# ProDocument_PCB6.net
KiCad netlist of a schematic drawn in EasyEDA Pro
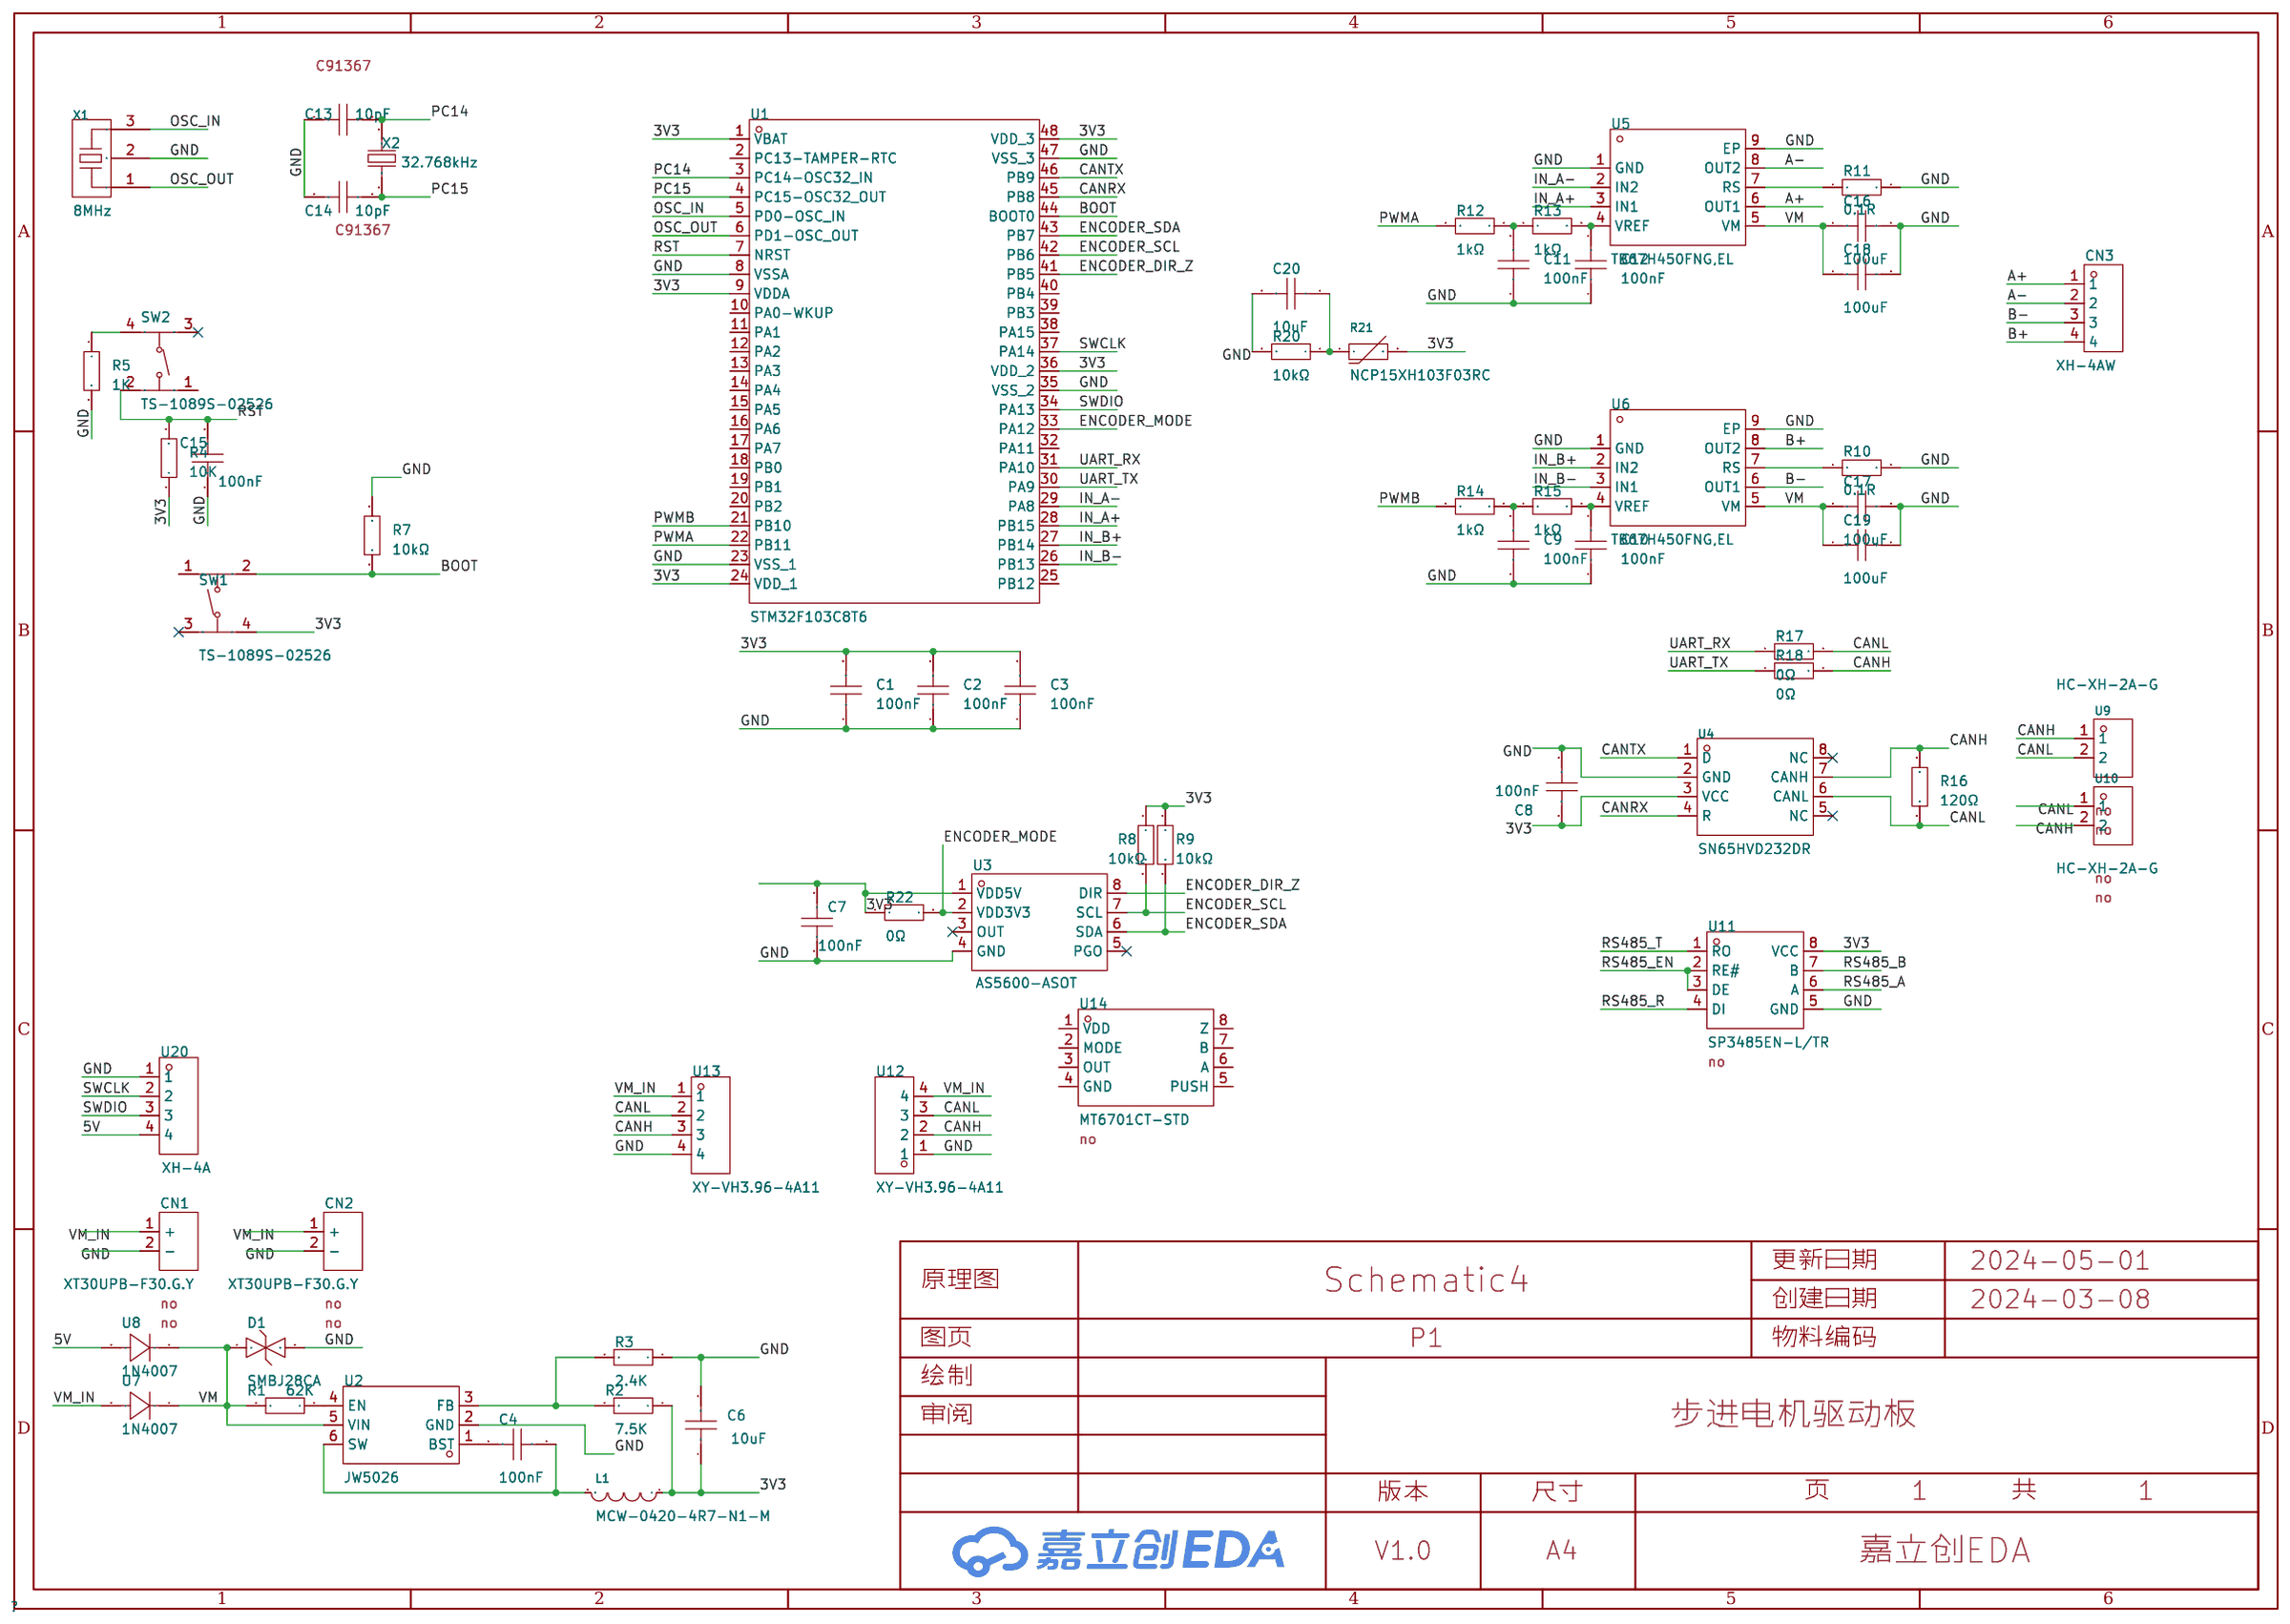
[diagram p0: schematic sheet]

(export (version "E")
  (design (tool "Eeschema 10.0.6"))
  (components
    (comp (ref "C1")
      (value "100nF")
      (description "容值:100nF;精度:±10%;额定电压:50V;材质(温度系数):X7R;")
      (fields (field (name "Manufacturer Part") "0603B104K500NT") (field (name "Manufacturer") "FH(风华)"))
      (libsource (lib "easyedapro") (part "CapAcitance"))
    )
    (comp (ref "C2")
      (value "100nF")
      (description "容值:100nF;精度:±10%;额定电压:50V;材质(温度系数):X7R;")
      (fields (field (name "Manufacturer Part") "0603B104K500NT") (field (name "Manufacturer") "FH(风华)"))
      (libsource (lib "easyedapro") (part "CapAcitance"))
    )
    (comp (ref "C3")
      (value "100nF")
      (description "容值:100nF;精度:±10%;额定电压:50V;材质(温度系数):X7R;")
      (fields (field (name "Manufacturer Part") "0603B104K500NT") (field (name "Manufacturer") "FH(风华)"))
      (libsource (lib "easyedapro") (part "CapAcitance"))
    )
    (comp (ref "C4")
      (value "100nF")
      (description "容值:100nF;精度:±10%;额定电压:50V;材质(温度系数):X7R;")
      (fields (field (name "Manufacturer Part") "0603B104K500NT") (field (name "Manufacturer") "FH(风华)"))
      (libsource (lib "easyedapro") (part "capacitance"))
    )
    (comp (ref "C6")
      (value "10uF")
      (description "容值:10uF;精度:±10%;额定电压:25V;材质(温度系数):X5R;")
      (fields
        (field (name "Manufacturer Part") "CL31A106KAHNNNE")
        (field (name "Manufacturer") "SAMSUNG(三星)")
      )
      (libsource (lib "easyedapro") (part "capacitance"))
    )
    (comp (ref "C7")
      (value "100nF")
      (fields (field (name "Manufacturer Part") "0603B104K500NT") (field (name "Manufacturer") "FH(风华)"))
      (libsource (lib "easyedapro") (part "CapAcitance"))
    )
    (comp (ref "C8")
      (value "100nF")
      (description "容值:100nF;精度:±10%;额定电压:50V;材质(温度系数):X7R;")
      (fields (field (name "Manufacturer Part") "0603B104K500NT") (field (name "Manufacturer") "FH(风华)"))
      (libsource (lib "easyedapro") (part "CapAcitance"))
    )
    (comp (ref "C9")
      (value "100nF")
      (description "容值:100nF;精度:±10%;额定电压:50V;材质(温度系数):X7R;")
      (fields (field (name "Manufacturer Part") "0603B104K500NT") (field (name "Manufacturer") "FH(风华)"))
      (libsource (lib "easyedapro") (part "CapAcitance"))
    )
    (comp (ref "C10")
      (value "100nF")
      (description "容值:100nF;精度:±10%;额定电压:50V;材质(温度系数):X7R;")
      (fields (field (name "Manufacturer Part") "0603B104K500NT") (field (name "Manufacturer") "FH(风华)"))
      (libsource (lib "easyedapro") (part "CapAcitance"))
    )
    (comp (ref "C11")
      (value "100nF")
      (description "容值:100nF;精度:±10%;额定电压:50V;材质(温度系数):X7R;")
      (fields (field (name "Manufacturer Part") "0603B104K500NT") (field (name "Manufacturer") "FH(风华)"))
      (libsource (lib "easyedapro") (part "CapAcitance"))
    )
    (comp (ref "C12")
      (value "100nF")
      (description "容值:100nF;精度:±10%;额定电压:50V;材质(温度系数):X7R;")
      (fields (field (name "Manufacturer Part") "0603B104K500NT") (field (name "Manufacturer") "FH(风华)"))
      (libsource (lib "easyedapro") (part "CapAcitance"))
    )
    (comp (ref "C13")
      (value "10pF")
      (fields
        (field (name "Manufacturer Part") "0603CG100J500NT")
        (field (name "Manufacturer") "FH(风华)")
        (field (name "Supplier Part") "C91367")
        (field (name "Tolerance") "±5%")
      )
      (libsource (lib "easyedapro") (part "capacitance"))
    )
    (comp (ref "C14")
      (value "10pF")
      (fields
        (field (name "Manufacturer Part") "0603CG100J500NT")
        (field (name "Manufacturer") "FH(风华)")
        (field (name "Supplier Part") "C91367")
        (field (name "Tolerance") "±5%")
      )
      (libsource (lib "easyedapro") (part "capacitance"))
    )
    (comp (ref "C15")
      (value "100nF")
      (description "容值:100nF;精度:±10%;额定电压:50V;材质(温度系数):X7R;")
      (fields (field (name "Manufacturer Part") "0603B104K500NT") (field (name "Manufacturer") "FH(风华)"))
      (libsource (lib "easyedapro") (part "CapAcitance"))
    )
    (comp (ref "C16")
      (value "100uF")
      (description "容值:4.7uF;精度:±10%;额定电压:50V;材质(温度系数):X7R;")
      (fields (field (name "Manufacturer Part") "1206B475K500NT") (field (name "Manufacturer") "FH(风华)"))
      (libsource (lib "easyedapro") (part "capacitance"))
    )
    (comp (ref "C17")
      (value "100uF")
      (description "容值:4.7uF;精度:±10%;额定电压:50V;材质(温度系数):X7R;")
      (fields (field (name "Manufacturer Part") "1206B475K500NT") (field (name "Manufacturer") "FH(风华)"))
      (libsource (lib "easyedapro") (part "capacitance"))
    )
    (comp (ref "C18")
      (value "100uF")
      (description "容值:4.7uF;精度:±10%;额定电压:50V;材质(温度系数):X7R;")
      (fields (field (name "Manufacturer Part") "1206B475K500NT") (field (name "Manufacturer") "FH(风华)"))
      (libsource (lib "easyedapro") (part "capacitance"))
    )
    (comp (ref "C19")
      (value "100uF")
      (description "容值:4.7uF;精度:±10%;额定电压:50V;材质(温度系数):X7R;")
      (fields (field (name "Manufacturer Part") "1206B475K500NT") (field (name "Manufacturer") "FH(风华)"))
      (libsource (lib "easyedapro") (part "capacitance"))
    )
    (comp (ref "C20")
      (value "10uF")
      (description "容值:100nF;精度:±10%;额定电压:50V;材质(温度系数):X7R;")
      (fields (field (name "Manufacturer Part") "0603B104K500NT") (field (name "Manufacturer") "FH(风华)"))
      (libsource (lib "easyedapro") (part "CapAcitance"))
    )
    (comp (ref "CN1")
      (value "XT30UPB-F30.G.Y")
      (footprint "easyedapro:CONN-TH_XT30UPB-F")
      (description "类别:-;类型1:-;")
      (fields
        (field (name "Manufacturer") "AMASS(艾迈斯)")
        (field (name "Add into BOM") "no")
        (field (name "Convert to PCB") "no")
      )
      (libsource (lib "easyedapro") (part "XT30UPB-F"))
    )
    (comp (ref "CN2")
      (value "XT30UPB-F30.G.Y")
      (footprint "easyedapro:CONN-TH_XT30UPB-F")
      (description "类别:-;类型1:-;")
      (fields
        (field (name "Manufacturer") "AMASS(艾迈斯)")
        (field (name "Add into BOM") "no")
        (field (name "Convert to PCB") "no")
      )
      (libsource (lib "easyedapro") (part "XT30UPB-F"))
    )
    (comp (ref "CN3")
      (value "XH-4AW")
      (footprint "easyedapro:CONN-TH_XH-4AW")
      (description "参考系列:XH;间距:2.54mm;插针结构:1x4P;排数:1;每排PIN数:4;行距:-;公母:公型插针;安装方式:弯插;额定电流:3A;工作温度范围:-25°C~+85°C;")
      (fields (field (name "Manufacturer") "HCTL(华灿天禄)"))
      (libsource (lib "easyedapro") (part "XH-4AW_C2908613"))
    )
    (comp (ref "D1")
      (value "SMBJ28CA")
      (footprint "easyedapro:SMB_L4.6-W3.6-LS5.3-BI")
      (description "极性：双向 反向截止电压(Vrwm)：28V 击穿电压：31.1V 最大钳位电压：45.4V")
      (fields (field (name "Manufacturer") "TWGMC(台湾迪嘉)"))
      (libsource (lib "easyedapro") (part "SMBJ28CA_C726872"))
    )
    (comp (ref "L1")
      (value "MCW-0420-4R7-N1-M")
      (footprint "easyedapro:IND-SMD_L4.5-W4.2")
      (fields (field (name "Manufacturer") "Hk-hotline(合泰盟方)"))
      (libsource (lib "easyedapro") (part "MCW-0420-4R7-N1"))
    )
    (comp (ref "R1")
      (value "62K")
      (description "电阻类型:厚膜电阻;阻值:62kΩ;精度:±1%;功率:100mW;最大工作电压:75V;温度系数:±100ppm/℃;")
      (fields
        (field (name "Manufacturer Part") "0603WAF6202T5E")
        (field (name "Manufacturer") "UNI-ROYAL(厚声)")
      )
      (libsource (lib "easyedapro") (part "电阻"))
    )
    (comp (ref "R2")
      (value "7.5K")
      (fields
        (field (name "Manufacturer Part") "0603WAF7501T5E")
        (field (name "Manufacturer") "UNI-ROYAL(厚声)")
      )
      (libsource (lib "easyedapro") (part "电阻"))
    )
    (comp (ref "R3")
      (value "2.4K")
      (fields
        (field (name "Manufacturer Part") "0603WAF2401T5E")
        (field (name "Manufacturer") "UNI-ROYAL(厚声)")
      )
      (libsource (lib "easyedapro") (part "电阻"))
    )
    (comp (ref "R4")
      (value "10K")
      (description "电阻类型:厚膜电阻;阻值:10kΩ;精度:±1%;功率:100mW;最大工作电压:75V;温度系数:±100ppm/℃;")
      (fields
        (field (name "Manufacturer Part") "0603WAF1002T5E")
        (field (name "Manufacturer") "UNI-ROYAL(厚声)")
      )
      (libsource (lib "easyedapro") (part "电阻"))
    )
    (comp (ref "R5")
      (value "1K")
      (fields (field (name "Manufacturer Part") "RC0603FR-071KL") (field (name "Manufacturer") "YAGEO(国巨)"))
      (libsource (lib "easyedapro") (part "电阻"))
    )
    (comp (ref "R7")
      (value "10kΩ")
      (description "电阻类型:厚膜电阻;阻值:10kΩ;精度:±1%;功率:100mW;最大工作电压:75V;温度系数:±100ppm/℃;")
      (fields
        (field (name "Manufacturer Part") "0603WAF1002T5E")
        (field (name "Manufacturer") "UNI-ROYAL(厚声)")
      )
      (libsource (lib "easyedapro") (part "电阻"))
    )
    (comp (ref "R8")
      (value "10kΩ")
      (description "电阻类型:厚膜电阻;阻值:10kΩ;精度:±1%;功率:100mW;最大工作电压:75V;温度系数:±100ppm/℃;")
      (fields
        (field (name "Manufacturer Part") "0603WAF1002T5E")
        (field (name "Manufacturer") "UNI-ROYAL(厚声)")
      )
      (libsource (lib "easyedapro") (part "电阻"))
    )
    (comp (ref "R9")
      (value "10kΩ")
      (description "电阻类型:厚膜电阻;阻值:10kΩ;精度:±1%;功率:100mW;最大工作电压:75V;温度系数:±100ppm/℃;")
      (fields
        (field (name "Manufacturer Part") "0603WAF1002T5E")
        (field (name "Manufacturer") "UNI-ROYAL(厚声)")
      )
      (libsource (lib "easyedapro") (part "电阻"))
    )
    (comp (ref "R10")
      (value "0.1R")
      (description "电阻类型:厚膜电阻;阻值:100mΩ;精度:±1%;功率:250mW;最大工作电压:200V;温度系数:±800ppm/℃;")
      (fields
        (field (name "Manufacturer Part") "1206W4F100LT5E")
        (field (name "Manufacturer") "UNI-ROYAL(厚声)")
      )
      (libsource (lib "easyedapro") (part "电阻"))
    )
    (comp (ref "R11")
      (value "0.1R")
      (description "电阻类型:厚膜电阻;阻值:100mΩ;精度:±1%;功率:250mW;最大工作电压:200V;温度系数:±800ppm/℃;")
      (fields
        (field (name "Manufacturer Part") "1206W4F100LT5E")
        (field (name "Manufacturer") "UNI-ROYAL(厚声)")
      )
      (libsource (lib "easyedapro") (part "电阻"))
    )
    (comp (ref "R12")
      (value "1kΩ")
      (fields (field (name "Manufacturer Part") "RC0603FR-071KL") (field (name "Manufacturer") "YAGEO(国巨)"))
      (libsource (lib "easyedapro") (part "电阻"))
    )
    (comp (ref "R13")
      (value "1kΩ")
      (fields (field (name "Manufacturer Part") "RC0603FR-071KL") (field (name "Manufacturer") "YAGEO(国巨)"))
      (libsource (lib "easyedapro") (part "电阻"))
    )
    (comp (ref "R14")
      (value "1kΩ")
      (fields (field (name "Manufacturer Part") "RC0603FR-071KL") (field (name "Manufacturer") "YAGEO(国巨)"))
      (libsource (lib "easyedapro") (part "电阻"))
    )
    (comp (ref "R15")
      (value "1kΩ")
      (fields (field (name "Manufacturer Part") "RC0603FR-071KL") (field (name "Manufacturer") "YAGEO(国巨)"))
      (libsource (lib "easyedapro") (part "电阻"))
    )
    (comp (ref "R16")
      (value "120Ω")
      (footprint "easyedapro:R0603")
      (description "电阻类型:厚膜电阻;阻值:120Ω;精度:±1%;功率:100mW;")
      (fields
        (field (name "Manufacturer Part") "0603WAF1200T5E")
        (field (name "Manufacturer") "UNI-ROYAL(厚声)")
      )
      (libsource (lib "easyedapro") (part "0603WAF1200T5E"))
    )
    (comp (ref "R17")
      (value "0Ω")
      (footprint "easyedapro:R0603")
      (description "电阻类型:厚膜电阻;阻值:0Ω;精度:±1%;功率:100mW;最大工作电压:75V;")
      (fields
        (field (name "Manufacturer Part") "0603WAF0000T5E")
        (field (name "Manufacturer") "UNI-ROYAL(厚声)")
      )
      (libsource (lib "easyedapro") (part "0603WAF0000T5E"))
    )
    (comp (ref "R18")
      (value "0Ω")
      (footprint "easyedapro:R0603")
      (description "电阻类型:厚膜电阻;阻值:0Ω;精度:±1%;功率:100mW;最大工作电压:75V;")
      (fields
        (field (name "Manufacturer Part") "0603WAF0000T5E")
        (field (name "Manufacturer") "UNI-ROYAL(厚声)")
      )
      (libsource (lib "easyedapro") (part "0603WAF0000T5E"))
    )
    (comp (ref "R20")
      (value "10kΩ")
      (description "电阻类型:厚膜电阻;阻值:10kΩ;精度:±1%;功率:100mW;最大工作电压:75V;温度系数:±100ppm/℃;")
      (fields
        (field (name "Manufacturer Part") "0603WAF1002T5E")
        (field (name "Manufacturer") "UNI-ROYAL(厚声)")
      )
      (libsource (lib "easyedapro") (part "电阻"))
    )
    (comp (ref "R21")
      (value "NCP15XH103F03RC")
      (footprint "easyedapro:R0402")
      (description "阻值(25°C):10kΩ;B值(25°C/50°C):3380K;电阻精度:±1%;功率:100mW;B值精度:±1%;最大稳态电流(25°C):310uA;")
      (fields (field (name "Manufacturer") "muRata(村田)"))
      (libsource (lib "easyedapro") (part "NCP15XH103F03RC"))
    )
    (comp (ref "R22")
      (value "0Ω")
      (footprint "easyedapro:R0603")
      (description "电阻类型:厚膜电阻;阻值:0Ω;精度:±1%;功率:100mW;最大工作电压:75V;")
      (fields
        (field (name "Manufacturer Part") "0603WAF0000T5E")
        (field (name "Manufacturer") "UNI-ROYAL(厚声)")
      )
      (libsource (lib "easyedapro") (part "0603WAF0000T5E"))
    )
    (comp (ref "SW1")
      (value "TS-1089S-02526")
      (footprint "easyedapro:SW-SMD_4P-L4.2-W3.3-P2.15-LS5.1")
      (description "触点电流:50mA;额定电压(DC):12V;电路结构:单刀单掷;安装方式:立贴;带灯:-;机械寿命:-;")
      (fields (field (name "Manufacturer") "XUNPU(讯普)"))
      (libsource (lib "easyedapro") (part "TS-1089S-02526"))
    )
    (comp (ref "SW2")
      (value "TS-1089S-02526")
      (footprint "easyedapro:SW-SMD_4P-L4.2-W3.3-P2.15-LS5.1")
      (description "触点电流:50mA;额定电压(DC):12V;电路结构:单刀单掷;安装方式:立贴;带灯:-;机械寿命:-;")
      (fields (field (name "Manufacturer") "XUNPU(讯普)"))
      (libsource (lib "easyedapro") (part "TS-1089S-02526"))
    )
    (comp (ref "U1")
      (value "STM32F103C8T6")
      (footprint "easyedapro:LQFP-48_L7.0-W7.0-P0.50-LS9.0-BL")
      (description "CPU内核:CM3;程序存储容量:64KB;RAM总容量:20KB;GPIO端口数量:37;工作电压范围:2V~3.6V;CPU最大主频:72MHz;程序存储器类型:FLASH;")
      (fields (field (name "Manufacturer") "ST(意法半导体)"))
      (libsource (lib "easyedapro") (part "STM32F103C8T6"))
    )
    (comp (ref "U2")
      (value "JW5026")
      (footprint "easyedapro:SOT-23-6_L2.9-W1.6-P0.95-LS2.8-BR")
      (description "功能类型:降压型;输入电压:-;输出电流(最大值):-;")
      (fields (field (name "Manufacturer") "Joulwatt(杰华特)"))
      (libsource (lib "easyedapro") (part "JW5026"))
    )
    (comp (ref "U3")
      (value "AS5600-ASOT")
      (footprint "easyedapro:SOIC-8_L5.0-W4.0-P1.27-LS6.0-BL")
      (fields (field (name "Manufacturer") "ams(艾迈斯半导体)"))
      (libsource (lib "easyedapro") (part "AS5600-ASOT"))
    )
    (comp (ref "U4")
      (value "SN65HVD232DR")
      (footprint "easyedapro:SOIC-8_L5.0-W4.0-P1.27-LS6.0-BL")
      (description "类型:收发器;数据速率:1Mbps;")
      (fields (field (name "Manufacturer") "TI(德州仪器)"))
      (libsource (lib "easyedapro") (part "SN65HVD232DR"))
    )
    (comp (ref "U5")
      (value "TB67H450FNG,EL")
      (footprint "easyedapro:HSOP-8_L5.0-W4.0-P1.27-LS6.2-BL-EP")
      (fields (field (name "Manufacturer") "TOSHIBA(东芝)"))
      (libsource (lib "easyedapro") (part "TB67H450FNG,EL"))
    )
    (comp (ref "U6")
      (value "TB67H450FNG,EL")
      (footprint "easyedapro:HSOP-8_L5.0-W4.0-P1.27-LS6.2-BL-EP")
      (fields (field (name "Manufacturer") "TOSHIBA(东芝)"))
      (libsource (lib "easyedapro") (part "TB67H450FNG,EL"))
    )
    (comp (ref "U7")
      (value "1N4007")
      (footprint "easyedapro:SMA_L4.3-W2.6-LS5.1-RD")
      (libsource (lib "easyedapro") (part "1N4007_C9900004759"))
    )
    (comp (ref "U8")
      (value "1N4007")
      (footprint "easyedapro:SMA_L4.3-W2.6-LS5.1-RD")
      (libsource (lib "easyedapro") (part "1N4007_C9900004759"))
    )
    (comp (ref "U9")
      (value "HC-XH-2A-G")
      (footprint "easyedapro:CONN-TH_2P-P2.50_HC-XH-2A-G")
      (description "参考系列:XH;间距:2.54mm;插针结构:1x2P;排数:1;每排PIN数:2;行距:2.54mm;公母:公型插针;安装方式:直插;额定电流:3A;工作温度范围:-25°C~+85°C;")
      (fields
        (field (name "Manufacturer") "HCTL(华灿天禄)")
        (field (name "Add into BOM") "no")
        (field (name "Convert to PCB") "no")
      )
      (libsource (lib "easyedapro") (part "HC-XH-2A-G"))
    )
    (comp (ref "U10")
      (value "HC-XH-2A-G")
      (footprint "easyedapro:CONN-TH_2P-P2.50_HC-XH-2A-G")
      (description "参考系列:XH;间距:2.54mm;插针结构:1x2P;排数:1;每排PIN数:2;行距:2.54mm;公母:公型插针;安装方式:直插;额定电流:3A;工作温度范围:-25°C~+85°C;")
      (fields
        (field (name "Manufacturer") "HCTL(华灿天禄)")
        (field (name "Add into BOM") "no")
        (field (name "Convert to PCB") "no")
      )
      (libsource (lib "easyedapro") (part "HC-XH-2A-G"))
    )
    (comp (ref "U11")
      (value "SP3485EN-L/TR")
      (footprint "easyedapro:SOIC-8_L5.0-W4.0-P1.27-LS6.0-BL")
      (description "类型:收发器;数据速率:10Mbps;驱动器/接收器:1/1;")
      (fields (field (name "Manufacturer") "MaxLinear(迈凌)") (field (name "Convert to PCB") "no"))
      (libsource (lib "easyedapro") (part "SP3485EN-L/TR"))
    )
    (comp (ref "U12")
      (value "XY-VH3.96-4A11")
      (footprint "easyedapro:CONN-TH_4P-P3.96_XYECONN_XY-VH3.96-4A11")
      (description "插针结构:1x4P;间距:3.96mm;安装方式:直插;总PIN数:4P;排数:1;每排PIN数:4;行距:3.96mm;额定电流:3A;工作温度范围:-25°C~+85°C;")
      (fields (field (name "Manufacturer") "XYECONN(辛译)"))
      (libsource (lib "easyedapro") (part "XY-VH3.96-4A11"))
    )
    (comp (ref "U13")
      (value "XY-VH3.96-4A11")
      (footprint "easyedapro:CONN-TH_4P-P3.96_XYECONN_XY-VH3.96-4A11")
      (description "插针结构:1x4P;间距:3.96mm;安装方式:直插;总PIN数:4P;排数:1;每排PIN数:4;行距:3.96mm;额定电流:3A;工作温度范围:-25°C~+85°C;")
      (fields (field (name "Manufacturer") "XYECONN(辛译)"))
      (libsource (lib "easyedapro") (part "XY-VH3.96-4A11"))
    )
    (comp (ref "U14")
      (value "MT6701CT-STD")
      (footprint "easyedapro:SOP-8_L4.9-W3.9-P1.27-LS6.0-BL")
      (fields (field (name "Manufacturer") "MagnTek(麦歌恩)") (field (name "Convert to PCB") "no"))
      (libsource (lib "easyedapro") (part "MT6701CT-STD_C5451785"))
    )
    (comp (ref "U20")
      (value "XH-4A")
      (footprint "easyedapro:CONN-TH_XH2.50-4P")
      (description "参考系列:XH;间距:2.5mm;插针结构:1x4P;排数:1;每排PIN数:4;行距:-;公母:公型插针;安装方式:直插;额定电流:3A;工作温度范围:-25°C~+85°C;")
      (fields (field (name "Manufacturer") "HCTL(华灿天禄)"))
      (libsource (lib "easyedapro") (part "XH-4A_C2908602"))
    )
    (comp (ref "X1")
      (value "8MHz")
      (footprint "easyedapro:OSC-SMD_3P-L3.2-W1.3-P1.2-L")
      (description "频率:8MHz;内置负载电容:33pF;谐振阻抗:40Ω;")
      (fields
        (field (name "Manufacturer Part") "CSTCE8M00G15C99-R0")
        (field (name "Manufacturer") "muRata(村田)")
      )
      (libsource (lib "easyedapro") (part "CSTCE8M00G15C99-R0"))
    )
    (comp (ref "X2")
      (value "32.768kHz")
      (fields (field (name "Manufacturer Part") "X321532768KGD2SI") (field (name "Manufacturer") "YXC(扬兴晶振)"))
      (libsource (lib "easyedapro") (part "Q13FC1350000400"))
    )
  )
  (nets
    (net (code "1") (name "/3V3") (class "Default")
      (node (ref "C1") (pin "2") (pinfunction "2_2") (pintype "input"))
      (node (ref "C2") (pin "2") (pinfunction "2_2") (pintype "input"))
      (node (ref "C3") (pin "2") (pinfunction "2_2") (pintype "input"))
      (node (ref "C6") (pin "1") (pinfunction "1_1") (pintype "input"))
      (node (ref "C7") (pin "2") (pinfunction "2_2") (pintype "input"))
      (node (ref "C8") (pin "2") (pinfunction "2_2") (pintype "input"))
      (node (ref "L1") (pin "1") (pinfunction "1_1") (pintype "input"))
      (node (ref "R2") (pin "1") (pinfunction "1_1") (pintype "input"))
      (node (ref "R21") (pin "2") (pinfunction "2_2") (pintype "input"))
      (node (ref "R22") (pin "1") (pinfunction "1_1") (pintype "input"))
      (node (ref "R4") (pin "1") (pinfunction "1_1") (pintype "input"))
      (node (ref "R8") (pin "1") (pinfunction "1_1") (pintype "input"))
      (node (ref "R9") (pin "1") (pinfunction "1_1") (pintype "input"))
      (node (ref "SW1") (pin "4") (pinfunction "4_4") (pintype "input"))
      (node (ref "U1") (pin "1") (pinfunction "VBAT_1") (pintype "unspecified"))
      (node (ref "U1") (pin "24") (pinfunction "VDD_1_24") (pintype "unspecified"))
      (node (ref "U1") (pin "36") (pinfunction "VDD_2_36") (pintype "unspecified"))
      (node (ref "U1") (pin "48") (pinfunction "VDD_3_48") (pintype "unspecified"))
      (node (ref "U1") (pin "9") (pinfunction "VDDA_9") (pintype "unspecified"))
      (node (ref "U11") (pin "8") (pinfunction "VCC_8") (pintype "unspecified"))
      (node (ref "U3") (pin "1") (pinfunction "VDD5V_1") (pintype "input"))
      (node (ref "U4") (pin "3") (pinfunction "VCC_3") (pintype "input"))
    )
    (net (code "2") (name "/5V") (class "Default")
      (node (ref "U20") (pin "4") (pinfunction "4_4") (pintype "input"))
      (node (ref "U8") (pin "2") (pinfunction "A_2") (pintype "input"))
    )
    (net (code "3") (name "/A+") (class "Default")
      (node (ref "CN3") (pin "1") (pinfunction "1_1") (pintype "input"))
      (node (ref "U5") (pin "6") (pinfunction "OUT1_6") (pintype "input"))
    )
    (net (code "4") (name "/A-") (class "Default")
      (node (ref "CN3") (pin "2") (pinfunction "2_2") (pintype "input"))
      (node (ref "U5") (pin "8") (pinfunction "OUT2_8") (pintype "input"))
    )
    (net (code "5") (name "/B+") (class "Default")
      (node (ref "CN3") (pin "4") (pinfunction "4_4") (pintype "input"))
      (node (ref "U6") (pin "8") (pinfunction "OUT2_8") (pintype "input"))
    )
    (net (code "6") (name "/B-") (class "Default")
      (node (ref "CN3") (pin "3") (pinfunction "3_3") (pintype "input"))
      (node (ref "U6") (pin "6") (pinfunction "OUT1_6") (pintype "input"))
    )
    (net (code "7") (name "/BOOT") (class "Default")
      (node (ref "R7") (pin "2") (pinfunction "2_2") (pintype "input"))
      (node (ref "SW1") (pin "2") (pinfunction "2_2") (pintype "input"))
      (node (ref "U1") (pin "44") (pinfunction "BOOT0_44") (pintype "unspecified"))
    )
    (net (code "8") (name "/CANH") (class "Default")
      (node (ref "R16") (pin "2") (pinfunction "2_2") (pintype "input"))
      (node (ref "R18") (pin "2") (pinfunction "2_2") (pintype "input"))
      (node (ref "U10") (pin "2") (pinfunction "2_2") (pintype "input"))
      (node (ref "U12") (pin "2") (pinfunction "2_2") (pintype "unspecified"))
      (node (ref "U13") (pin "3") (pinfunction "3_3") (pintype "unspecified"))
      (node (ref "U4") (pin "7") (pinfunction "CANH_7") (pintype "input"))
      (node (ref "U9") (pin "1") (pinfunction "1_1") (pintype "input"))
    )
    (net (code "9") (name "/CANL") (class "Default")
      (node (ref "R16") (pin "1") (pinfunction "1_1") (pintype "input"))
      (node (ref "R17") (pin "2") (pinfunction "2_2") (pintype "input"))
      (node (ref "U10") (pin "1") (pinfunction "1_1") (pintype "input"))
      (node (ref "U12") (pin "3") (pinfunction "3_3") (pintype "unspecified"))
      (node (ref "U13") (pin "2") (pinfunction "2_2") (pintype "unspecified"))
      (node (ref "U4") (pin "6") (pinfunction "CANL_6") (pintype "input"))
      (node (ref "U9") (pin "2") (pinfunction "2_2") (pintype "input"))
    )
    (net (code "10") (name "/CANRX") (class "Default")
      (node (ref "U1") (pin "45") (pinfunction "PB8_45") (pintype "unspecified"))
      (node (ref "U4") (pin "4") (pinfunction "R_4") (pintype "input"))
    )
    (net (code "11") (name "/CANTX") (class "Default")
      (node (ref "U1") (pin "46") (pinfunction "PB9_46") (pintype "unspecified"))
      (node (ref "U4") (pin "1") (pinfunction "D_1") (pintype "input"))
    )
    (net (code "12") (name "/ENCODER_DIR_Z") (class "Default")
      (node (ref "U1") (pin "41") (pinfunction "PB5_41") (pintype "unspecified"))
      (node (ref "U3") (pin "8") (pinfunction "DIR_8") (pintype "input"))
    )
    (net (code "13") (name "/ENCODER_MODE") (class "Default")
      (node (ref "R22") (pin "2") (pinfunction "2_2") (pintype "input"))
      (node (ref "U1") (pin "33") (pinfunction "PA12_33") (pintype "unspecified"))
      (node (ref "U3") (pin "2") (pinfunction "VDD3V3_2") (pintype "input"))
    )
    (net (code "14") (name "/ENCODER_SCL") (class "Default")
      (node (ref "R8") (pin "2") (pinfunction "2_2") (pintype "input"))
      (node (ref "U1") (pin "42") (pinfunction "PB6_42") (pintype "unspecified"))
      (node (ref "U3") (pin "7") (pinfunction "SCL_7") (pintype "input"))
    )
    (net (code "15") (name "/ENCODER_SDA") (class "Default")
      (node (ref "R9") (pin "2") (pinfunction "2_2") (pintype "input"))
      (node (ref "U1") (pin "43") (pinfunction "PB7_43") (pintype "unspecified"))
      (node (ref "U3") (pin "6") (pinfunction "SDA_6") (pintype "input"))
    )
    (net (code "16") (name "/GND") (class "Default")
      (node (ref "C1") (pin "1") (pinfunction "1_1") (pintype "input"))
      (node (ref "C10") (pin "1") (pinfunction "1_1") (pintype "input"))
      (node (ref "C11") (pin "1") (pinfunction "1_1") (pintype "input"))
      (node (ref "C12") (pin "1") (pinfunction "1_1") (pintype "input"))
      (node (ref "C13") (pin "1") (pinfunction "1_1") (pintype "input"))
      (node (ref "C14") (pin "1") (pinfunction "1_1") (pintype "input"))
      (node (ref "C15") (pin "1") (pinfunction "1_1") (pintype "input"))
      (node (ref "C16") (pin "2") (pinfunction "2_2") (pintype "input"))
      (node (ref "C17") (pin "2") (pinfunction "2_2") (pintype "input"))
      (node (ref "C18") (pin "2") (pinfunction "2_2") (pintype "input"))
      (node (ref "C19") (pin "2") (pinfunction "2_2") (pintype "input"))
      (node (ref "C2") (pin "1") (pinfunction "1_1") (pintype "input"))
      (node (ref "C20") (pin "2") (pinfunction "2_2") (pintype "input"))
      (node (ref "C3") (pin "1") (pinfunction "1_1") (pintype "input"))
      (node (ref "C6") (pin "2") (pinfunction "2_2") (pintype "input"))
      (node (ref "C7") (pin "1") (pinfunction "1_1") (pintype "input"))
      (node (ref "C8") (pin "1") (pinfunction "1_1") (pintype "input"))
      (node (ref "C9") (pin "1") (pinfunction "1_1") (pintype "input"))
      (node (ref "CN1") (pin "2") (pinfunction "-_2") (pintype "unspecified"))
      (node (ref "CN2") (pin "2") (pinfunction "-_2") (pintype "unspecified"))
      (node (ref "D1") (pin "2") (pinfunction "2_2") (pintype "unspecified"))
      (node (ref "R10") (pin "2") (pinfunction "2_2") (pintype "input"))
      (node (ref "R11") (pin "2") (pinfunction "2_2") (pintype "input"))
      (node (ref "R20") (pin "2") (pinfunction "2_2") (pintype "input"))
      (node (ref "R3") (pin "1") (pinfunction "1_1") (pintype "input"))
      (node (ref "R5") (pin "2") (pinfunction "2_2") (pintype "input"))
      (node (ref "R7") (pin "1") (pinfunction "1_1") (pintype "input"))
      (node (ref "U1") (pin "23") (pinfunction "VSS_1_23") (pintype "unspecified"))
      (node (ref "U1") (pin "35") (pinfunction "VSS_2_35") (pintype "unspecified"))
      (node (ref "U1") (pin "47") (pinfunction "VSS_3_47") (pintype "unspecified"))
      (node (ref "U1") (pin "8") (pinfunction "VSSA_8") (pintype "unspecified"))
      (node (ref "U11") (pin "5") (pinfunction "GND_5") (pintype "unspecified"))
      (node (ref "U12") (pin "1") (pinfunction "1_1") (pintype "unspecified"))
      (node (ref "U13") (pin "4") (pinfunction "4_4") (pintype "unspecified"))
      (node (ref "U2") (pin "2") (pinfunction "GND_2") (pintype "unspecified"))
      (node (ref "U20") (pin "1") (pinfunction "1_1") (pintype "input"))
      (node (ref "U3") (pin "4") (pinfunction "GND_4") (pintype "input"))
      (node (ref "U4") (pin "2") (pinfunction "GND_2") (pintype "input"))
      (node (ref "U5") (pin "1") (pinfunction "GND_1") (pintype "input"))
      (node (ref "U5") (pin "9") (pinfunction "EP_9") (pintype "input"))
      (node (ref "U6") (pin "1") (pinfunction "GND_1") (pintype "input"))
      (node (ref "U6") (pin "9") (pinfunction "EP_9") (pintype "input"))
      (node (ref "X1") (pin "2") (pinfunction "2_2") (pintype "input"))
    )
    (net (code "17") (name "/IN_A+") (class "Default")
      (node (ref "U1") (pin "28") (pinfunction "PB15_28") (pintype "unspecified"))
      (node (ref "U5") (pin "3") (pinfunction "IN1_3") (pintype "input"))
    )
    (net (code "18") (name "/IN_A-") (class "Default")
      (node (ref "U1") (pin "29") (pinfunction "PA8_29") (pintype "unspecified"))
      (node (ref "U5") (pin "2") (pinfunction "IN2_2") (pintype "input"))
    )
    (net (code "19") (name "/IN_B+") (class "Default")
      (node (ref "U1") (pin "27") (pinfunction "PB14_27") (pintype "unspecified"))
      (node (ref "U6") (pin "2") (pinfunction "IN2_2") (pintype "input"))
    )
    (net (code "20") (name "/IN_B-") (class "Default")
      (node (ref "U1") (pin "26") (pinfunction "PB13_26") (pintype "unspecified"))
      (node (ref "U6") (pin "3") (pinfunction "IN1_3") (pintype "input"))
    )
    (net (code "21") (name "/OSC_IN") (class "Default")
      (node (ref "U1") (pin "5") (pinfunction "PD0-OSC_IN_5") (pintype "unspecified"))
      (node (ref "X1") (pin "3") (pinfunction "3_3") (pintype "input"))
    )
    (net (code "22") (name "/OSC_OUT") (class "Default")
      (node (ref "U1") (pin "6") (pinfunction "PD1-OSC_OUT_6") (pintype "unspecified"))
      (node (ref "X1") (pin "1") (pinfunction "1_1") (pintype "input"))
    )
    (net (code "23") (name "/PC14") (class "Default")
      (node (ref "C13") (pin "2") (pinfunction "2_2") (pintype "input"))
      (node (ref "U1") (pin "3") (pinfunction "PC14-OSC32_IN_3") (pintype "unspecified"))
      (node (ref "X2") (pin "2") (pinfunction "2_2") (pintype "input"))
    )
    (net (code "24") (name "/PC15") (class "Default")
      (node (ref "C14") (pin "2") (pinfunction "2_2") (pintype "input"))
      (node (ref "U1") (pin "4") (pinfunction "PC15-OSC32_OUT_4") (pintype "unspecified"))
      (node (ref "X2") (pin "1") (pinfunction "1_1") (pintype "input"))
    )
    (net (code "25") (name "/PWMA") (class "Default")
      (node (ref "R12") (pin "2") (pinfunction "2_2") (pintype "input"))
      (node (ref "U1") (pin "22") (pinfunction "PB11_22") (pintype "unspecified"))
    )
    (net (code "26") (name "/PWMB") (class "Default")
      (node (ref "R14") (pin "2") (pinfunction "2_2") (pintype "input"))
      (node (ref "U1") (pin "21") (pinfunction "PB10_21") (pintype "unspecified"))
    )
    (net (code "27") (name "/RS485_A") (class "Default")
      (node (ref "U11") (pin "6") (pinfunction "A_6") (pintype "unspecified"))
    )
    (net (code "28") (name "/RS485_B") (class "Default")
      (node (ref "U11") (pin "7") (pinfunction "B_7") (pintype "unspecified"))
    )
    (net (code "29") (name "/RS485_EN") (class "Default")
      (node (ref "U11") (pin "2") (pinfunction "RE#_2") (pintype "unspecified"))
      (node (ref "U11") (pin "3") (pinfunction "DE_3") (pintype "unspecified"))
    )
    (net (code "30") (name "/RS485_R") (class "Default")
      (node (ref "U11") (pin "4") (pinfunction "DI_4") (pintype "unspecified"))
    )
    (net (code "31") (name "/RS485_T") (class "Default")
      (node (ref "U11") (pin "1") (pinfunction "RO_1") (pintype "unspecified"))
    )
    (net (code "32") (name "/RST") (class "Default")
      (node (ref "C15") (pin "2") (pinfunction "2_2") (pintype "input"))
      (node (ref "R4") (pin "2") (pinfunction "2_2") (pintype "input"))
      (node (ref "SW2") (pin "2") (pinfunction "2_2") (pintype "input"))
      (node (ref "U1") (pin "7") (pinfunction "NRST_7") (pintype "unspecified"))
    )
    (net (code "33") (name "/SWCLK") (class "Default")
      (node (ref "U1") (pin "37") (pinfunction "PA14_37") (pintype "unspecified"))
      (node (ref "U20") (pin "2") (pinfunction "2_2") (pintype "input"))
    )
    (net (code "34") (name "/SWDIO") (class "Default")
      (node (ref "U1") (pin "34") (pinfunction "PA13_34") (pintype "unspecified"))
      (node (ref "U20") (pin "3") (pinfunction "3_3") (pintype "input"))
    )
    (net (code "35") (name "/UART_RX") (class "Default")
      (node (ref "R17") (pin "1") (pinfunction "1_1") (pintype "input"))
      (node (ref "U1") (pin "31") (pinfunction "PA10_31") (pintype "unspecified"))
    )
    (net (code "36") (name "/UART_TX") (class "Default")
      (node (ref "R18") (pin "1") (pinfunction "1_1") (pintype "input"))
      (node (ref "U1") (pin "30") (pinfunction "PA9_30") (pintype "unspecified"))
    )
    (net (code "37") (name "/VM") (class "Default")
      (node (ref "C16") (pin "1") (pinfunction "1_1") (pintype "input"))
      (node (ref "C17") (pin "1") (pinfunction "1_1") (pintype "input"))
      (node (ref "C18") (pin "1") (pinfunction "1_1") (pintype "input"))
      (node (ref "C19") (pin "1") (pinfunction "1_1") (pintype "input"))
      (node (ref "D1") (pin "1") (pinfunction "1_1") (pintype "unspecified"))
      (node (ref "R1") (pin "2") (pinfunction "2_2") (pintype "input"))
      (node (ref "U2") (pin "5") (pinfunction "VIN_5") (pintype "unspecified"))
      (node (ref "U5") (pin "5") (pinfunction "VM_5") (pintype "input"))
      (node (ref "U6") (pin "5") (pinfunction "VM_5") (pintype "input"))
      (node (ref "U7") (pin "1") (pinfunction "K_1") (pintype "input"))
      (node (ref "U8") (pin "1") (pinfunction "K_1") (pintype "input"))
    )
    (net (code "38") (name "/VM_IN") (class "Default")
      (node (ref "CN1") (pin "1") (pinfunction "+_1") (pintype "unspecified"))
      (node (ref "CN2") (pin "1") (pinfunction "+_1") (pintype "unspecified"))
      (node (ref "U12") (pin "4") (pinfunction "4_4") (pintype "unspecified"))
      (node (ref "U13") (pin "1") (pinfunction "1_1") (pintype "unspecified"))
      (node (ref "U7") (pin "2") (pinfunction "A_2") (pintype "input"))
    )
    (net (code "39") (name "Net-(C9-Pad2)") (class "Default")
      (node (ref "C9") (pin "2") (pinfunction "2_2") (pintype "input"))
      (node (ref "R14") (pin "1") (pinfunction "1_1") (pintype "input"))
      (node (ref "R15") (pin "1") (pinfunction "1_1") (pintype "input"))
    )
    (net (code "40") (name "Net-(C11-Pad2)") (class "Default")
      (node (ref "C11") (pin "2") (pinfunction "2_2") (pintype "input"))
      (node (ref "R12") (pin "1") (pinfunction "1_1") (pintype "input"))
      (node (ref "R13") (pin "1") (pinfunction "1_1") (pintype "input"))
    )
    (net (code "41") (name "Net-(C20-Pad1)") (class "Default")
      (node (ref "C20") (pin "1") (pinfunction "1_1") (pintype "input"))
      (node (ref "R20") (pin "1") (pinfunction "1_1") (pintype "input"))
      (node (ref "R21") (pin "1") (pinfunction "1_1") (pintype "input"))
    )
    (net (code "42") (name "Net-(R5-Pad1)") (class "Default")
      (node (ref "R5") (pin "1") (pinfunction "1_1") (pintype "input"))
      (node (ref "SW2") (pin "4") (pinfunction "4_4") (pintype "input"))
    )
    (net (code "43") (name "Net-(U2-BST)") (class "Default")
      (node (ref "C4") (pin "1") (pinfunction "1_1") (pintype "input"))
      (node (ref "U2") (pin "1") (pinfunction "BST_1") (pintype "unspecified"))
    )
    (net (code "44") (name "Net-(U2-EN)") (class "Default")
      (node (ref "R1") (pin "1") (pinfunction "1_1") (pintype "input"))
      (node (ref "U2") (pin "4") (pinfunction "EN_4") (pintype "unspecified"))
    )
    (net (code "45") (name "Net-(U2-FB)") (class "Default")
      (node (ref "R2") (pin "2") (pinfunction "2_2") (pintype "input"))
      (node (ref "R3") (pin "2") (pinfunction "2_2") (pintype "input"))
      (node (ref "U2") (pin "3") (pinfunction "FB_3") (pintype "unspecified"))
    )
    (net (code "46") (name "Net-(U2-SW)") (class "Default")
      (node (ref "C4") (pin "2") (pinfunction "2_2") (pintype "input"))
      (node (ref "L1") (pin "2") (pinfunction "2_2") (pintype "input"))
      (node (ref "U2") (pin "6") (pinfunction "SW_6") (pintype "unspecified"))
    )
    (net (code "47") (name "Net-(U5-RS)") (class "Default")
      (node (ref "R11") (pin "1") (pinfunction "1_1") (pintype "input"))
      (node (ref "U5") (pin "7") (pinfunction "RS_7") (pintype "input"))
    )
    (net (code "48") (name "Net-(U5-VREF)") (class "Default")
      (node (ref "C12") (pin "2") (pinfunction "2_2") (pintype "input"))
      (node (ref "R13") (pin "2") (pinfunction "2_2") (pintype "input"))
      (node (ref "U5") (pin "4") (pinfunction "VREF_4") (pintype "input"))
    )
    (net (code "49") (name "Net-(U6-RS)") (class "Default")
      (node (ref "R10") (pin "1") (pinfunction "1_1") (pintype "input"))
      (node (ref "U6") (pin "7") (pinfunction "RS_7") (pintype "input"))
    )
    (net (code "50") (name "Net-(U6-VREF)") (class "Default")
      (node (ref "C10") (pin "2") (pinfunction "2_2") (pintype "input"))
      (node (ref "R15") (pin "2") (pinfunction "2_2") (pintype "input"))
      (node (ref "U6") (pin "4") (pinfunction "VREF_4") (pintype "input"))
    )
    (net (code "51") (name "unconnected-(SW1-Pad1)") (class "Default")
      (node (ref "SW1") (pin "1") (pinfunction "1_1") (pintype "input"))
    )
    (net (code "52") (name "unconnected-(SW1-Pad3)") (class "Default")
      (node (ref "SW1") (pin "3") (pinfunction "3_3") (pintype "input+no_connect"))
    )
    (net (code "53") (name "unconnected-(SW2-Pad1)") (class "Default")
      (node (ref "SW2") (pin "1") (pinfunction "1_1") (pintype "input"))
    )
    (net (code "54") (name "unconnected-(SW2-Pad3)") (class "Default")
      (node (ref "SW2") (pin "3") (pinfunction "3_3") (pintype "input+no_connect"))
    )
    (net (code "55") (name "unconnected-(U1-PA0-WKUP-Pad10)") (class "Default")
      (node (ref "U1") (pin "10") (pinfunction "PA0-WKUP_10") (pintype "unspecified"))
    )
    (net (code "56") (name "unconnected-(U1-PA1-Pad11)") (class "Default")
      (node (ref "U1") (pin "11") (pinfunction "PA1_11") (pintype "unspecified"))
    )
    (net (code "57") (name "unconnected-(U1-PA2-Pad12)") (class "Default")
      (node (ref "U1") (pin "12") (pinfunction "PA2_12") (pintype "unspecified"))
    )
    (net (code "58") (name "unconnected-(U1-PA3-Pad13)") (class "Default")
      (node (ref "U1") (pin "13") (pinfunction "PA3_13") (pintype "unspecified"))
    )
    (net (code "59") (name "unconnected-(U1-PA4-Pad14)") (class "Default")
      (node (ref "U1") (pin "14") (pinfunction "PA4_14") (pintype "unspecified"))
    )
    (net (code "60") (name "unconnected-(U1-PA5-Pad15)") (class "Default")
      (node (ref "U1") (pin "15") (pinfunction "PA5_15") (pintype "unspecified"))
    )
    (net (code "61") (name "unconnected-(U1-PA6-Pad16)") (class "Default")
      (node (ref "U1") (pin "16") (pinfunction "PA6_16") (pintype "unspecified"))
    )
    (net (code "62") (name "unconnected-(U1-PA7-Pad17)") (class "Default")
      (node (ref "U1") (pin "17") (pinfunction "PA7_17") (pintype "unspecified"))
    )
    (net (code "63") (name "unconnected-(U1-PA11-Pad32)") (class "Default")
      (node (ref "U1") (pin "32") (pinfunction "PA11_32") (pintype "unspecified"))
    )
    (net (code "64") (name "unconnected-(U1-PA15-Pad38)") (class "Default")
      (node (ref "U1") (pin "38") (pinfunction "PA15_38") (pintype "unspecified"))
    )
    (net (code "65") (name "unconnected-(U1-PB0-Pad18)") (class "Default")
      (node (ref "U1") (pin "18") (pinfunction "PB0_18") (pintype "unspecified"))
    )
    (net (code "66") (name "unconnected-(U1-PB1-Pad19)") (class "Default")
      (node (ref "U1") (pin "19") (pinfunction "PB1_19") (pintype "unspecified"))
    )
    (net (code "67") (name "unconnected-(U1-PB2-Pad20)") (class "Default")
      (node (ref "U1") (pin "20") (pinfunction "PB2_20") (pintype "unspecified"))
    )
    (net (code "68") (name "unconnected-(U1-PB3-Pad39)") (class "Default")
      (node (ref "U1") (pin "39") (pinfunction "PB3_39") (pintype "unspecified"))
    )
    (net (code "69") (name "unconnected-(U1-PB4-Pad40)") (class "Default")
      (node (ref "U1") (pin "40") (pinfunction "PB4_40") (pintype "unspecified"))
    )
    (net (code "70") (name "unconnected-(U1-PB12-Pad25)") (class "Default")
      (node (ref "U1") (pin "25") (pinfunction "PB12_25") (pintype "unspecified"))
    )
    (net (code "71") (name "unconnected-(U1-PC13-TAMPER-RTC-Pad2)") (class "Default")
      (node (ref "U1") (pin "2") (pinfunction "PC13-TAMPER-RTC_2") (pintype "unspecified"))
    )
    (net (code "72") (name "unconnected-(U3-OUT-Pad3)") (class "Default")
      (node (ref "U3") (pin "3") (pinfunction "OUT_3") (pintype "input+no_connect"))
    )
    (net (code "73") (name "unconnected-(U3-PGO-Pad5)") (class "Default")
      (node (ref "U3") (pin "5") (pinfunction "PGO_5") (pintype "input+no_connect"))
    )
    (net (code "74") (name "unconnected-(U4-NC-Pad5)") (class "Default")
      (node (ref "U4") (pin "5") (pinfunction "NC_5") (pintype "input+no_connect"))
    )
    (net (code "75") (name "unconnected-(U4-NC-Pad8)") (class "Default")
      (node (ref "U4") (pin "8") (pinfunction "NC_8") (pintype "input+no_connect"))
    )
    (net (code "76") (name "unconnected-(U14-A-Pad6)") (class "Default")
      (node (ref "U14") (pin "6") (pinfunction "A_6") (pintype "unspecified"))
    )
    (net (code "77") (name "unconnected-(U14-B-Pad7)") (class "Default")
      (node (ref "U14") (pin "7") (pinfunction "B_7") (pintype "unspecified"))
    )
    (net (code "78") (name "unconnected-(U14-GND-Pad4)") (class "Default")
      (node (ref "U14") (pin "4") (pinfunction "GND_4") (pintype "unspecified"))
    )
    (net (code "79") (name "unconnected-(U14-MODE-Pad2)") (class "Default")
      (node (ref "U14") (pin "2") (pinfunction "MODE_2") (pintype "unspecified"))
    )
    (net (code "80") (name "unconnected-(U14-OUT-Pad3)") (class "Default")
      (node (ref "U14") (pin "3") (pinfunction "OUT_3") (pintype "unspecified"))
    )
    (net (code "81") (name "unconnected-(U14-PUSH-Pad5)") (class "Default")
      (node (ref "U14") (pin "5") (pinfunction "PUSH_5") (pintype "unspecified"))
    )
    (net (code "82") (name "unconnected-(U14-VDD-Pad1)") (class "Default")
      (node (ref "U14") (pin "1") (pinfunction "VDD_1") (pintype "unspecified"))
    )
    (net (code "83") (name "unconnected-(U14-Z-Pad8)") (class "Default")
      (node (ref "U14") (pin "8") (pinfunction "Z_8") (pintype "unspecified"))
    )
  )
)
